# 4channelsRelayv2.net
KiCad netlist of a schematic drawn in EAGLE
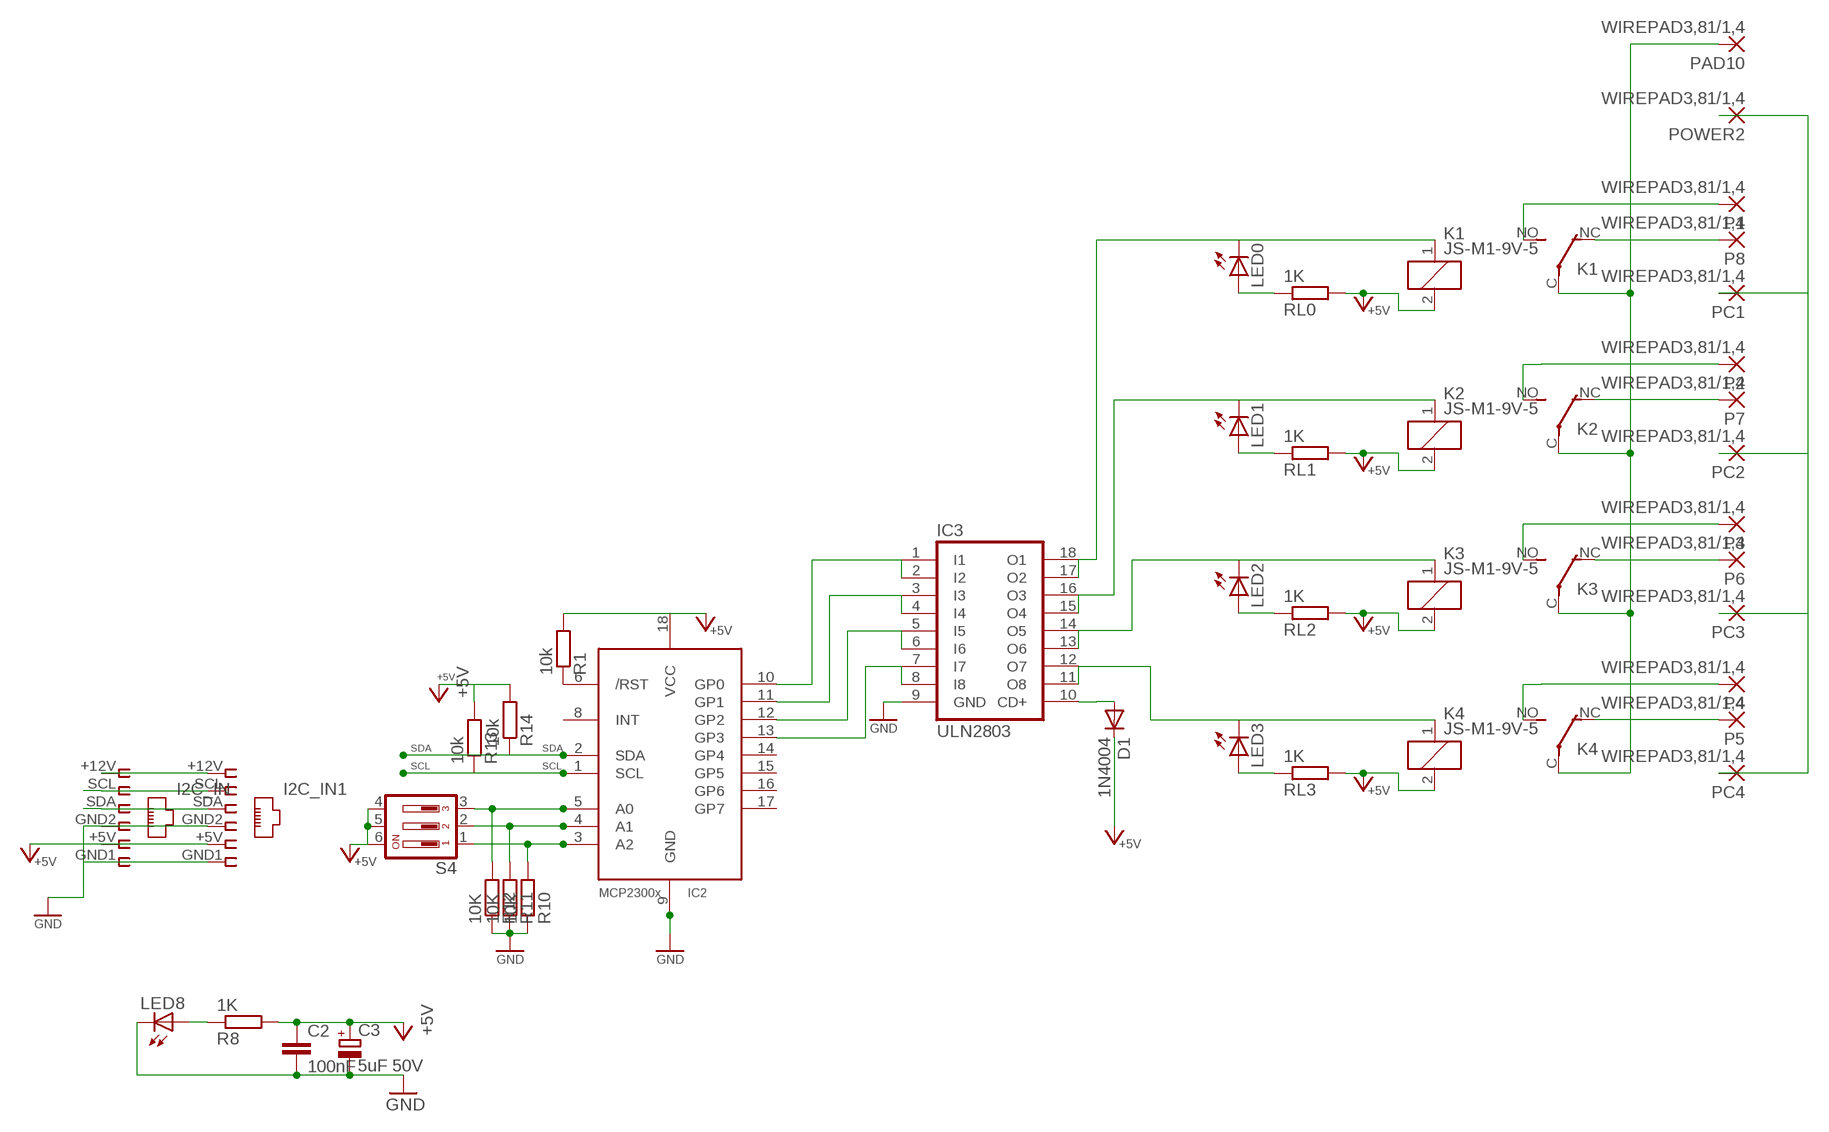
[diagram p0: schematic, sheet 1]

(export (version "E")
  (design (tool "Eeschema 10.0.6"))
  (components
    (comp (ref "C2")
      (value "100nF")
      (footprint "eagle-import:C1206")
      (libsource (lib "eagle-import") (part "C-EUC1206"))
    )
    (comp (ref "C3")
      (value "5uF 50V")
      (footprint "eagle-import:E3,5-8")
      (libsource (lib "eagle-import") (part "CPOL-EUE3.5-8"))
    )
    (comp (ref "D1")
      (value "1N4004")
      (footprint "eagle-import:DO41-10")
      (libsource (lib "eagle-import") (part "1N4004"))
    )
    (comp (ref "I2C_IN")
      (value "I2C 1")
      (footprint "eagle-import:RJ12-STRAIGHT-I2C")
      (libsource (lib "eagle-import") (part "RJ12STRAIGHT-I2C"))
    )
    (comp (ref "I2C_IN1")
      (value "I2C 2")
      (footprint "eagle-import:RJ12-STRAIGHT-I2C")
      (libsource (lib "eagle-import") (part "RJ12STRAIGHT-I2C"))
    )
    (comp (ref "IC2")
      (value "MCP2300X/P")
      (footprint "eagle-import:DIL18")
      (libsource (lib "eagle-import") (part "MCP2300X/P"))
    )
    (comp (ref "IC3")
      (value "ULN2803")
      (footprint "eagle-import:DIL18")
      (libsource (lib "eagle-import") (part "ULN2803A"))
    )
    (comp (ref "K1")
      (value "JS-M1-9V-5")
      (footprint "eagle-import:JS-M")
      (libsource (lib "eagle-import") (part "JS-M1-9V-5"))
    )
    (comp (ref "K2")
      (value "JS-M1-9V-5")
      (footprint "eagle-import:JS-M")
      (libsource (lib "eagle-import") (part "JS-M1-9V-5"))
    )
    (comp (ref "K3")
      (value "JS-M1-9V-5")
      (footprint "eagle-import:JS-M")
      (libsource (lib "eagle-import") (part "JS-M1-9V-5"))
    )
    (comp (ref "K4")
      (value "JS-M1-9V-5")
      (footprint "eagle-import:JS-M")
      (libsource (lib "eagle-import") (part "JS-M1-9V-5"))
    )
    (comp (ref "LED0")
      (value "LED3MM")
      (footprint "eagle-import:LED3MM")
      (libsource (lib "eagle-import") (part "LED3MM"))
    )
    (comp (ref "LED1")
      (value "LED3MM")
      (footprint "eagle-import:LED3MM")
      (libsource (lib "eagle-import") (part "LED3MM"))
    )
    (comp (ref "LED2")
      (value "LED3MM")
      (footprint "eagle-import:LED3MM")
      (libsource (lib "eagle-import") (part "LED3MM"))
    )
    (comp (ref "LED3")
      (value "LED3MM")
      (footprint "eagle-import:LED3MM")
      (libsource (lib "eagle-import") (part "LED3MM"))
    )
    (comp (ref "LED8")
      (value "LED3MM")
      (footprint "eagle-import:LED3MM")
      (libsource (lib "eagle-import") (part "LED3MM"))
    )
    (comp (ref "P1")
      (value "WIREPAD3,81/1,4")
      (footprint "eagle-import:3,81_1,4")
      (libsource (lib "eagle-import") (part "WIREPAD3,81/1,4"))
    )
    (comp (ref "P2")
      (value "WIREPAD3,81/1,4")
      (footprint "eagle-import:3,81_1,4")
      (libsource (lib "eagle-import") (part "WIREPAD3,81/1,4"))
    )
    (comp (ref "P3")
      (value "WIREPAD3,81/1,4")
      (footprint "eagle-import:3,81_1,4")
      (libsource (lib "eagle-import") (part "WIREPAD3,81/1,4"))
    )
    (comp (ref "P4")
      (value "WIREPAD3,81/1,4")
      (footprint "eagle-import:3,81_1,4")
      (libsource (lib "eagle-import") (part "WIREPAD3,81/1,4"))
    )
    (comp (ref "P5")
      (value "WIREPAD3,81/1,4")
      (footprint "eagle-import:3,81_1,4")
      (libsource (lib "eagle-import") (part "WIREPAD3,81/1,4"))
    )
    (comp (ref "P6")
      (value "WIREPAD3,81/1,4")
      (footprint "eagle-import:3,81_1,4")
      (libsource (lib "eagle-import") (part "WIREPAD3,81/1,4"))
    )
    (comp (ref "P7")
      (value "WIREPAD3,81/1,4")
      (footprint "eagle-import:3,81_1,4")
      (libsource (lib "eagle-import") (part "WIREPAD3,81/1,4"))
    )
    (comp (ref "P8")
      (value "WIREPAD3,81/1,4")
      (footprint "eagle-import:3,81_1,4")
      (libsource (lib "eagle-import") (part "WIREPAD3,81/1,4"))
    )
    (comp (ref "PAD10")
      (value "WIREPAD3,81/1,4")
      (footprint "eagle-import:3,81_1,4")
      (libsource (lib "eagle-import") (part "WIREPAD3,81/1,4"))
    )
    (comp (ref "PC1")
      (value "WIREPAD3,81/1,4")
      (footprint "eagle-import:3,81_1,4")
      (libsource (lib "eagle-import") (part "WIREPAD3,81/1,4"))
    )
    (comp (ref "PC2")
      (value "WIREPAD3,81/1,4")
      (footprint "eagle-import:3,81_1,4")
      (libsource (lib "eagle-import") (part "WIREPAD3,81/1,4"))
    )
    (comp (ref "PC3")
      (value "WIREPAD3,81/1,4")
      (footprint "eagle-import:3,81_1,4")
      (libsource (lib "eagle-import") (part "WIREPAD3,81/1,4"))
    )
    (comp (ref "PC4")
      (value "WIREPAD3,81/1,4")
      (footprint "eagle-import:3,81_1,4")
      (libsource (lib "eagle-import") (part "WIREPAD3,81/1,4"))
    )
    (comp (ref "POWER2")
      (value "WIREPAD3,81/1,4")
      (footprint "eagle-import:3,81_1,4")
      (libsource (lib "eagle-import") (part "WIREPAD3,81/1,4"))
    )
    (comp (ref "R1")
      (value "10k")
      (footprint "eagle-import:M1206")
      (libsource (lib "eagle-import") (part "R-EU_M1206"))
    )
    (comp (ref "R8")
      (value "1K")
      (footprint "eagle-import:M1206")
      (libsource (lib "eagle-import") (part "R-EU_M1206"))
    )
    (comp (ref "R10")
      (value "10K")
      (footprint "eagle-import:M1206")
      (libsource (lib "eagle-import") (part "R-EU_M1206"))
    )
    (comp (ref "R11")
      (value "10K")
      (footprint "eagle-import:M1206")
      (libsource (lib "eagle-import") (part "R-EU_M1206"))
    )
    (comp (ref "R12")
      (value "10K")
      (footprint "eagle-import:M1206")
      (libsource (lib "eagle-import") (part "R-EU_M1206"))
    )
    (comp (ref "R13")
      (value "10k")
      (footprint "eagle-import:M1206")
      (libsource (lib "eagle-import") (part "R-EU_M1206"))
    )
    (comp (ref "R14")
      (value "10k")
      (footprint "eagle-import:M1206")
      (libsource (lib "eagle-import") (part "R-EU_M1206"))
    )
    (comp (ref "RL0")
      (value "1K")
      (footprint "eagle-import:M1206")
      (libsource (lib "eagle-import") (part "R-EU_M1206"))
    )
    (comp (ref "RL1")
      (value "1K")
      (footprint "eagle-import:M1206")
      (libsource (lib "eagle-import") (part "R-EU_M1206"))
    )
    (comp (ref "RL2")
      (value "1K")
      (footprint "eagle-import:M1206")
      (libsource (lib "eagle-import") (part "R-EU_M1206"))
    )
    (comp (ref "RL3")
      (value "1K")
      (footprint "eagle-import:M1206")
      (libsource (lib "eagle-import") (part "R-EU_M1206"))
    )
    (comp (ref "S4")
      (value "DIP03YL")
      (footprint "eagle-import:DIP03YL")
      (libsource (lib "eagle-import") (part "DIP03YL"))
    )
  )
  (nets
    (net (code "1") (name "+5V") (class "Default")
      (node (ref "C2") (pin "1") (pinfunction "1_1") (pintype "passive"))
      (node (ref "C3") (pin "+") (pinfunction "+_+") (pintype "passive"))
      (node (ref "D1") (pin "C") (pinfunction "C_C") (pintype "passive"))
      (node (ref "I2C_IN") (pin "+5V") (pinfunction "5_+5V") (pintype "power_in"))
      (node (ref "I2C_IN1") (pin "+5V") (pinfunction "5_+5V") (pintype "power_in"))
      (node (ref "IC2") (pin "18") (pinfunction "VCC_18") (pintype "power_in"))
      (node (ref "K1") (pin "2") (pinfunction "2_2") (pintype "passive"))
      (node (ref "K2") (pin "2") (pinfunction "2_2") (pintype "passive"))
      (node (ref "K3") (pin "2") (pinfunction "2_2") (pintype "passive"))
      (node (ref "K4") (pin "2") (pinfunction "2_2") (pintype "passive"))
      (node (ref "R1") (pin "2") (pinfunction "2_2") (pintype "passive"))
      (node (ref "R13") (pin "2") (pinfunction "2_2") (pintype "passive"))
      (node (ref "R14") (pin "2") (pinfunction "2_2") (pintype "passive"))
      (node (ref "R8") (pin "2") (pinfunction "2_2") (pintype "passive"))
      (node (ref "RL0") (pin "2") (pinfunction "2_2") (pintype "passive"))
      (node (ref "RL1") (pin "2") (pinfunction "2_2") (pintype "passive"))
      (node (ref "RL2") (pin "2") (pinfunction "2_2") (pintype "passive"))
      (node (ref "RL3") (pin "2") (pinfunction "2_2") (pintype "passive"))
      (node (ref "S4") (pin "4") (pinfunction "4_4") (pintype "passive"))
      (node (ref "S4") (pin "5") (pinfunction "5_5") (pintype "passive"))
      (node (ref "S4") (pin "6") (pinfunction "6_6") (pintype "passive"))
    )
    (net (code "2") (name "/SCL") (class "Default")
      (node (ref "I2C_IN") (pin "SCL") (pinfunction "2_SCL") (pintype "bidirectional"))
      (node (ref "I2C_IN1") (pin "SCL") (pinfunction "2_SCL") (pintype "bidirectional"))
      (node (ref "IC2") (pin "1") (pinfunction "SCL_1") (pintype "bidirectional"))
      (node (ref "R13") (pin "1") (pinfunction "1_1") (pintype "passive"))
    )
    (net (code "3") (name "/SDA") (class "Default")
      (node (ref "I2C_IN") (pin "SDA") (pinfunction "3_SDA") (pintype "bidirectional"))
      (node (ref "I2C_IN1") (pin "SDA") (pinfunction "3_SDA") (pintype "bidirectional"))
      (node (ref "IC2") (pin "2") (pinfunction "SDA_2") (pintype "bidirectional"))
      (node (ref "R14") (pin "1") (pinfunction "1_1") (pintype "passive"))
    )
    (net (code "4") (name "GND") (class "Default")
      (node (ref "C2") (pin "2") (pinfunction "2_2") (pintype "passive"))
      (node (ref "C3") (pin "-") (pinfunction "-_-") (pintype "passive"))
      (node (ref "I2C_IN") (pin "GND1") (pinfunction "6_GND1") (pintype "power_in"))
      (node (ref "I2C_IN") (pin "GND2") (pinfunction "4_GND2") (pintype "power_in"))
      (node (ref "I2C_IN1") (pin "GND1") (pinfunction "6_GND1") (pintype "power_in"))
      (node (ref "I2C_IN1") (pin "GND2") (pinfunction "4_GND2") (pintype "power_in"))
      (node (ref "IC2") (pin "9") (pinfunction "GND_9") (pintype "power_in"))
      (node (ref "IC3") (pin "9") (pinfunction "GND_9") (pintype "power_in"))
      (node (ref "LED8") (pin "K") (pinfunction "C_K") (pintype "passive"))
      (node (ref "R10") (pin "1") (pinfunction "1_1") (pintype "passive"))
      (node (ref "R11") (pin "1") (pinfunction "1_1") (pintype "passive"))
      (node (ref "R12") (pin "1") (pinfunction "1_1") (pintype "passive"))
    )
    (net (code "5") (name "Net-(I2C_IN-1)") (class "Default")
      (node (ref "I2C_IN") (pin "+12V") (pinfunction "1_+12V") (pintype "power_in"))
      (node (ref "I2C_IN1") (pin "+12V") (pinfunction "1_+12V") (pintype "power_in"))
    )
    (net (code "6") (name "Net-(IC2-A0)") (class "Default")
      (node (ref "IC2") (pin "5") (pinfunction "A0_5") (pintype "input"))
      (node (ref "R12") (pin "2") (pinfunction "2_2") (pintype "passive"))
      (node (ref "S4") (pin "3") (pinfunction "3_3") (pintype "passive"))
    )
    (net (code "7") (name "Net-(IC2-A1)") (class "Default")
      (node (ref "IC2") (pin "4") (pinfunction "A1_4") (pintype "input"))
      (node (ref "R11") (pin "2") (pinfunction "2_2") (pintype "passive"))
      (node (ref "S4") (pin "2") (pinfunction "2_2") (pintype "passive"))
    )
    (net (code "8") (name "Net-(IC2-A2)") (class "Default")
      (node (ref "IC2") (pin "3") (pinfunction "A2_3") (pintype "input"))
      (node (ref "R10") (pin "2") (pinfunction "2_2") (pintype "passive"))
      (node (ref "S4") (pin "1") (pinfunction "1_1") (pintype "passive"))
    )
    (net (code "9") (name "Net-(IC2-GP0)") (class "Default")
      (node (ref "IC2") (pin "10") (pinfunction "GP0_10") (pintype "bidirectional"))
      (node (ref "IC3") (pin "1") (pinfunction "I1_1") (pintype "input"))
      (node (ref "IC3") (pin "2") (pinfunction "I2_2") (pintype "input"))
    )
    (net (code "10") (name "Net-(IC2-GP1)") (class "Default")
      (node (ref "IC2") (pin "11") (pinfunction "GP1_11") (pintype "bidirectional"))
      (node (ref "IC3") (pin "3") (pinfunction "I3_3") (pintype "input"))
      (node (ref "IC3") (pin "4") (pinfunction "I4_4") (pintype "input"))
    )
    (net (code "11") (name "Net-(IC2-GP2)") (class "Default")
      (node (ref "IC2") (pin "12") (pinfunction "GP2_12") (pintype "bidirectional"))
      (node (ref "IC3") (pin "5") (pinfunction "I5_5") (pintype "input"))
      (node (ref "IC3") (pin "6") (pinfunction "I6_6") (pintype "input"))
    )
    (net (code "12") (name "Net-(IC2-GP3)") (class "Default")
      (node (ref "IC2") (pin "13") (pinfunction "GP3_13") (pintype "bidirectional"))
      (node (ref "IC3") (pin "7") (pinfunction "I7_7") (pintype "input"))
      (node (ref "IC3") (pin "8") (pinfunction "I8_8") (pintype "input"))
    )
    (net (code "13") (name "Net-(IC2-{slash}RST)") (class "Default")
      (node (ref "IC2") (pin "6") (pinfunction "/RST_6") (pintype "input"))
      (node (ref "R1") (pin "1") (pinfunction "1_1") (pintype "passive"))
    )
    (net (code "14") (name "Net-(IC3-CD+)") (class "Default")
      (node (ref "D1") (pin "A") (pinfunction "A_A") (pintype "passive"))
      (node (ref "IC3") (pin "10") (pinfunction "CD+_10") (pintype "passive"))
    )
    (net (code "15") (name "Net-(IC3-O1)") (class "Default")
      (node (ref "IC3") (pin "17") (pinfunction "O2_17") (pintype "open_collector"))
      (node (ref "IC3") (pin "18") (pinfunction "O1_18") (pintype "open_collector"))
      (node (ref "K1") (pin "1") (pinfunction "1_1") (pintype "passive"))
      (node (ref "LED0") (pin "K") (pinfunction "C_K") (pintype "passive"))
    )
    (net (code "16") (name "Net-(IC3-O3)") (class "Default")
      (node (ref "IC3") (pin "15") (pinfunction "O4_15") (pintype "open_collector"))
      (node (ref "IC3") (pin "16") (pinfunction "O3_16") (pintype "open_collector"))
      (node (ref "K2") (pin "1") (pinfunction "1_1") (pintype "passive"))
      (node (ref "LED1") (pin "K") (pinfunction "C_K") (pintype "passive"))
    )
    (net (code "17") (name "Net-(IC3-O5)") (class "Default")
      (node (ref "IC3") (pin "13") (pinfunction "O6_13") (pintype "open_collector"))
      (node (ref "IC3") (pin "14") (pinfunction "O5_14") (pintype "open_collector"))
      (node (ref "K3") (pin "1") (pinfunction "1_1") (pintype "passive"))
      (node (ref "LED2") (pin "K") (pinfunction "C_K") (pintype "passive"))
    )
    (net (code "18") (name "Net-(IC3-O7)") (class "Default")
      (node (ref "IC3") (pin "11") (pinfunction "O8_11") (pintype "open_collector"))
      (node (ref "IC3") (pin "12") (pinfunction "O7_12") (pintype "open_collector"))
      (node (ref "K4") (pin "1") (pinfunction "1_1") (pintype "passive"))
      (node (ref "LED3") (pin "K") (pinfunction "C_K") (pintype "passive"))
    )
    (net (code "19") (name "Net-(K1B-O)") (class "Default")
      (node (ref "K1") (pin "NC") (pinfunction "O_NC") (pintype "passive"))
      (node (ref "P8") (pin "1") (pinfunction "P_1") (pintype "passive"))
    )
    (net (code "20") (name "Net-(K1B-P)") (class "Default")
      (node (ref "K1") (pin "C") (pinfunction "P_C") (pintype "passive"))
      (node (ref "K2") (pin "C") (pinfunction "P_C") (pintype "passive"))
      (node (ref "K3") (pin "C") (pinfunction "P_C") (pintype "passive"))
      (node (ref "K4") (pin "C") (pinfunction "P_C") (pintype "passive"))
      (node (ref "PAD10") (pin "1") (pinfunction "P_1") (pintype "passive"))
    )
    (net (code "21") (name "Net-(K1B-S)") (class "Default")
      (node (ref "K1") (pin "NO") (pinfunction "S_NO") (pintype "passive"))
      (node (ref "P1") (pin "1") (pinfunction "P_1") (pintype "passive"))
    )
    (net (code "22") (name "Net-(K2B-O)") (class "Default")
      (node (ref "K2") (pin "NC") (pinfunction "O_NC") (pintype "passive"))
      (node (ref "P7") (pin "1") (pinfunction "P_1") (pintype "passive"))
    )
    (net (code "23") (name "Net-(K2B-S)") (class "Default")
      (node (ref "K2") (pin "NO") (pinfunction "S_NO") (pintype "passive"))
      (node (ref "P2") (pin "1") (pinfunction "P_1") (pintype "passive"))
    )
    (net (code "24") (name "Net-(K3B-O)") (class "Default")
      (node (ref "K3") (pin "NC") (pinfunction "O_NC") (pintype "passive"))
      (node (ref "P6") (pin "1") (pinfunction "P_1") (pintype "passive"))
    )
    (net (code "25") (name "Net-(K3B-S)") (class "Default")
      (node (ref "K3") (pin "NO") (pinfunction "S_NO") (pintype "passive"))
      (node (ref "P3") (pin "1") (pinfunction "P_1") (pintype "passive"))
    )
    (net (code "26") (name "Net-(K4B-O)") (class "Default")
      (node (ref "K4") (pin "NC") (pinfunction "O_NC") (pintype "passive"))
      (node (ref "P5") (pin "1") (pinfunction "P_1") (pintype "passive"))
    )
    (net (code "27") (name "Net-(K4B-S)") (class "Default")
      (node (ref "K4") (pin "NO") (pinfunction "S_NO") (pintype "passive"))
      (node (ref "P4") (pin "1") (pinfunction "P_1") (pintype "passive"))
    )
    (net (code "28") (name "Net-(LED0-PadA)") (class "Default")
      (node (ref "LED0") (pin "A") (pinfunction "A_A") (pintype "passive"))
      (node (ref "RL0") (pin "1") (pinfunction "1_1") (pintype "passive"))
    )
    (net (code "29") (name "Net-(LED1-PadA)") (class "Default")
      (node (ref "LED1") (pin "A") (pinfunction "A_A") (pintype "passive"))
      (node (ref "RL1") (pin "1") (pinfunction "1_1") (pintype "passive"))
    )
    (net (code "30") (name "Net-(LED2-PadA)") (class "Default")
      (node (ref "LED2") (pin "A") (pinfunction "A_A") (pintype "passive"))
      (node (ref "RL2") (pin "1") (pinfunction "1_1") (pintype "passive"))
    )
    (net (code "31") (name "Net-(LED3-PadA)") (class "Default")
      (node (ref "LED3") (pin "A") (pinfunction "A_A") (pintype "passive"))
      (node (ref "RL3") (pin "1") (pinfunction "1_1") (pintype "passive"))
    )
    (net (code "32") (name "Net-(LED8-PadA)") (class "Default")
      (node (ref "LED8") (pin "A") (pinfunction "A_A") (pintype "passive"))
      (node (ref "R8") (pin "1") (pinfunction "1_1") (pintype "passive"))
    )
    (net (code "33") (name "Net-(PC1-P)") (class "Default")
      (node (ref "PC1") (pin "1") (pinfunction "P_1") (pintype "passive"))
      (node (ref "PC2") (pin "1") (pinfunction "P_1") (pintype "passive"))
      (node (ref "PC3") (pin "1") (pinfunction "P_1") (pintype "passive"))
      (node (ref "PC4") (pin "1") (pinfunction "P_1") (pintype "passive"))
      (node (ref "POWER2") (pin "1") (pinfunction "P_1") (pintype "passive"))
    )
    (net (code "34") (name "unconnected-(IC2-GP4-Pad14)") (class "Default")
      (node (ref "IC2") (pin "14") (pinfunction "GP4_14") (pintype "bidirectional"))
    )
    (net (code "35") (name "unconnected-(IC2-GP5-Pad15)") (class "Default")
      (node (ref "IC2") (pin "15") (pinfunction "GP5_15") (pintype "bidirectional"))
    )
    (net (code "36") (name "unconnected-(IC2-GP6-Pad16)") (class "Default")
      (node (ref "IC2") (pin "16") (pinfunction "GP6_16") (pintype "bidirectional"))
    )
    (net (code "37") (name "unconnected-(IC2-GP7-Pad17)") (class "Default")
      (node (ref "IC2") (pin "17") (pinfunction "GP7_17") (pintype "bidirectional"))
    )
    (net (code "38") (name "unconnected-(IC2-INT-Pad8)") (class "Default")
      (node (ref "IC2") (pin "8") (pinfunction "INT_8") (pintype "output"))
    )
  )
)
